# supply.net
KiCad netlist of a schematic drawn in EAGLE
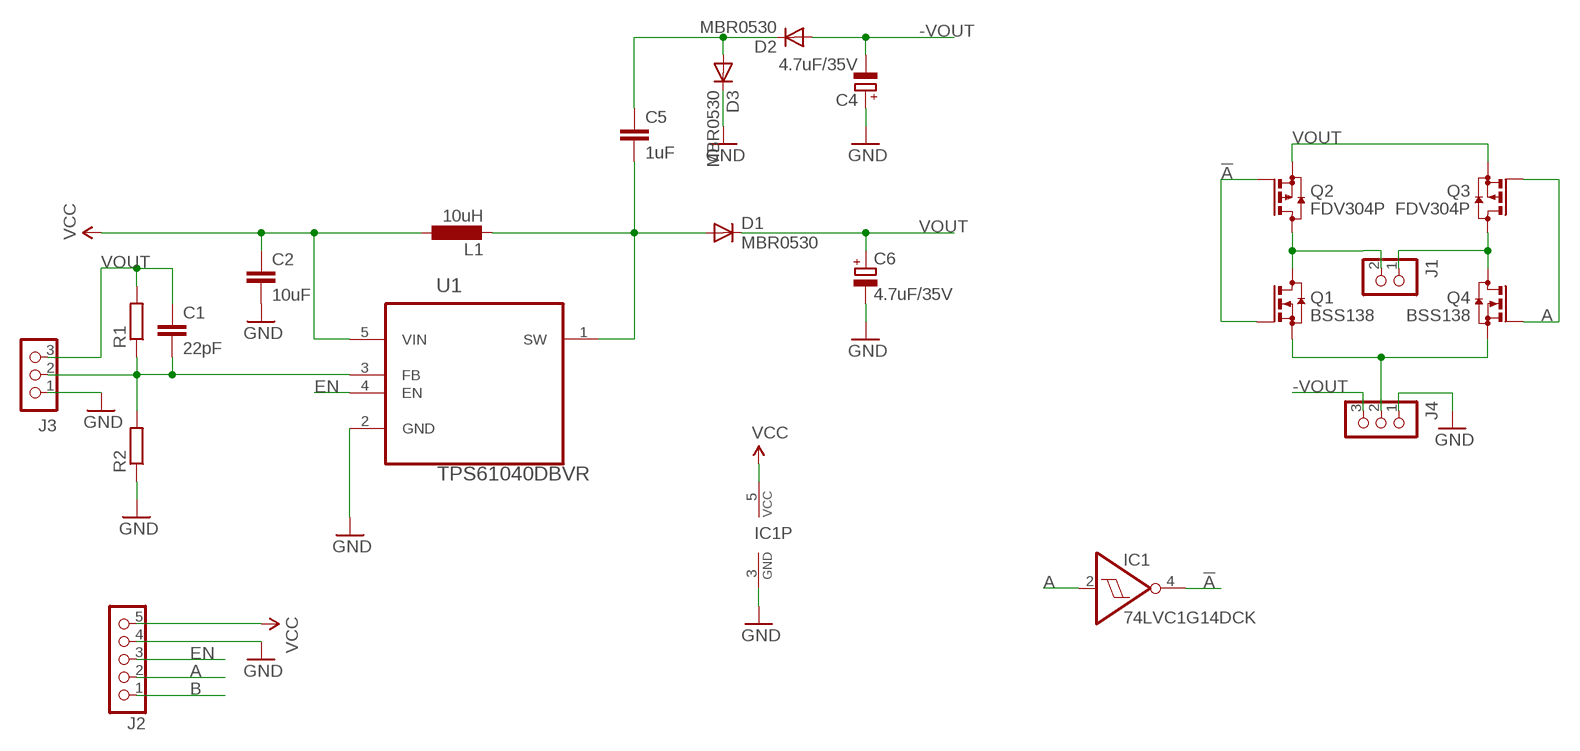
[diagram p0: schematic, sheet 1]

(export (version "E")
  (design (tool "Eeschema 10.0.6"))
  (components
    (comp (ref "C1")
      (value "22pF")
      (footprint "eagle-import:C0603")
      (libsource (lib "eagle-import") (part "C-EUC0603"))
    )
    (comp (ref "C2")
      (value "10uF")
      (footprint "eagle-import:C0603")
      (libsource (lib "eagle-import") (part "C-EUC0603"))
    )
    (comp (ref "C4")
      (value "4.7uF/35V")
      (footprint "eagle-import:140CLH-1010")
      (libsource (lib "eagle-import") (part "CPOL-EU140CLH-1010"))
    )
    (comp (ref "C5")
      (value "1uF")
      (footprint "eagle-import:C0603")
      (libsource (lib "eagle-import") (part "C-EUC0603"))
    )
    (comp (ref "C6")
      (value "4.7uF/35V")
      (footprint "eagle-import:140CLH-1010")
      (libsource (lib "eagle-import") (part "CPOL-EU140CLH-1010"))
    )
    (comp (ref "D1")
      (value "MBR0530")
      (footprint "eagle-import:SOD123")
      (libsource (lib "eagle-import") (part "DIODE-SOD123"))
    )
    (comp (ref "D2")
      (value "MBR0530")
      (footprint "eagle-import:SOD123")
      (libsource (lib "eagle-import") (part "DIODE-SOD123"))
    )
    (comp (ref "D3")
      (value "MBR0530")
      (footprint "eagle-import:SOD123")
      (libsource (lib "eagle-import") (part "DIODE-SOD123"))
    )
    (comp (ref "IC1")
      (value "74LVC1G14DCK")
      (footprint "eagle-import:SC70-5")
      (libsource (lib "eagle-import") (part "741G14DCKLVC"))
    )
    (comp (ref "J1")
      (value "CON_HEADER_1X02-PTH")
      (footprint "eagle-import:M1X2")
      (libsource (lib "eagle-import") (part "CON_HEADER_1X02-PTH"))
    )
    (comp (ref "J2")
      (value "CON_HEADER_1X05-PTH")
      (footprint "eagle-import:M1X5")
      (libsource (lib "eagle-import") (part "CON_HEADER_1X05-PTH"))
    )
    (comp (ref "J3")
      (value "CON_HEADER_1X03-PTH")
      (footprint "eagle-import:M1X3")
      (libsource (lib "eagle-import") (part "CON_HEADER_1X03-PTH"))
    )
    (comp (ref "J4")
      (value "CON_HEADER_1X03-PTH")
      (footprint "eagle-import:M1X3")
      (libsource (lib "eagle-import") (part "CON_HEADER_1X03-PTH"))
    )
    (comp (ref "L1")
      (value "10uH")
      (footprint "eagle-import:L2825P")
      (libsource (lib "eagle-import") (part "L-EUL2825P"))
    )
    (comp (ref "Q1")
      (value "BSS138")
      (footprint "eagle-import:SOT23")
      (libsource (lib "eagle-import") (part "BSS123"))
    )
    (comp (ref "Q2")
      (value "FDV304P")
      (footprint "eagle-import:SOT23")
      (libsource (lib "eagle-import") (part "BSS84"))
    )
    (comp (ref "Q3")
      (value "FDV304P")
      (footprint "eagle-import:SOT23")
      (libsource (lib "eagle-import") (part "BSS84"))
    )
    (comp (ref "Q4")
      (value "BSS138")
      (footprint "eagle-import:SOT23")
      (libsource (lib "eagle-import") (part "BSS123"))
    )
    (comp (ref "R1")
      (value "R-EU_R0603")
      (footprint "eagle-import:R0603")
      (libsource (lib "eagle-import") (part "R-EU_R0603"))
    )
    (comp (ref "R2")
      (value "R-EU_R0603")
      (footprint "eagle-import:R0603")
      (libsource (lib "eagle-import") (part "R-EU_R0603"))
    )
    (comp (ref "U1")
      (value "TPS61040DBVR")
      (footprint "eagle-import:SOT95P280X145-5N")
      (libsource (lib "eagle-import") (part "TPS61040DBVR"))
    )
  )
  (nets
    (net (code "1") (name "/-VOUT") (class "Default")
      (node (ref "C4") (pin "-") (pinfunction "-_-") (pintype "passive"))
      (node (ref "D2") (pin "A") (pinfunction "A_A") (pintype "passive"))
      (node (ref "J4") (pin "3") (pinfunction "3_3") (pintype "bidirectional"))
    )
    (net (code "2") (name "/A") (class "Default")
      (node (ref "IC1") (pin "2") (pinfunction "I_2") (pintype "input"))
      (node (ref "J2") (pin "2") (pinfunction "2_2") (pintype "bidirectional"))
      (node (ref "Q3") (pin "1") (pinfunction "G_1") (pintype "passive"))
      (node (ref "Q4") (pin "1") (pinfunction "G_1") (pintype "passive"))
    )
    (net (code "3") (name "/B") (class "Default")
      (node (ref "J2") (pin "1") (pinfunction "1_1") (pintype "bidirectional"))
    )
    (net (code "4") (name "/EN") (class "Default")
      (node (ref "J2") (pin "3") (pinfunction "3_3") (pintype "bidirectional"))
      (node (ref "U1") (pin "4") (pinfunction "EN_4") (pintype "input"))
    )
    (net (code "5") (name "/VOUT") (class "Default")
      (node (ref "C1") (pin "1") (pinfunction "1_1") (pintype "passive"))
      (node (ref "C6") (pin "+") (pinfunction "+_+") (pintype "passive"))
      (node (ref "D1") (pin "C") (pinfunction "C_C") (pintype "passive"))
      (node (ref "J3") (pin "3") (pinfunction "3_3") (pintype "bidirectional"))
      (node (ref "Q2") (pin "2") (pinfunction "S_2") (pintype "passive"))
      (node (ref "Q3") (pin "2") (pinfunction "S_2") (pintype "passive"))
      (node (ref "R1") (pin "2") (pinfunction "2_2") (pintype "passive"))
    )
    (net (code "6") (name "/~{A}") (class "Default")
      (node (ref "IC1") (pin "4") (pinfunction "O_4") (pintype "output"))
      (node (ref "Q1") (pin "1") (pinfunction "G_1") (pintype "passive"))
      (node (ref "Q2") (pin "1") (pinfunction "G_1") (pintype "passive"))
    )
    (net (code "7") (name "GND") (class "Default")
      (node (ref "C2") (pin "2") (pinfunction "2_2") (pintype "passive"))
      (node (ref "C4") (pin "+") (pinfunction "+_+") (pintype "passive"))
      (node (ref "C6") (pin "-") (pinfunction "-_-") (pintype "passive"))
      (node (ref "D3") (pin "C") (pinfunction "C_C") (pintype "passive"))
      (node (ref "IC1") (pin "3") (pinfunction "GND_3") (pintype "power_in"))
      (node (ref "J2") (pin "4") (pinfunction "4_4") (pintype "bidirectional"))
      (node (ref "J3") (pin "1") (pinfunction "1_1") (pintype "bidirectional"))
      (node (ref "J4") (pin "1") (pinfunction "1_1") (pintype "bidirectional"))
      (node (ref "R2") (pin "1") (pinfunction "1_1") (pintype "passive"))
      (node (ref "U1") (pin "2") (pinfunction "GND_2") (pintype "passive"))
    )
    (net (code "8") (name "Net-(C5-Pad1)") (class "Default")
      (node (ref "C5") (pin "1") (pinfunction "1_1") (pintype "passive"))
      (node (ref "D2") (pin "C") (pinfunction "C_C") (pintype "passive"))
      (node (ref "D3") (pin "A") (pinfunction "A_A") (pintype "passive"))
    )
    (net (code "9") (name "Net-(Q1-D)") (class "Default")
      (node (ref "J1") (pin "2") (pinfunction "2_2") (pintype "passive"))
      (node (ref "Q1") (pin "3") (pinfunction "D_3") (pintype "passive"))
      (node (ref "Q2") (pin "3") (pinfunction "D_3") (pintype "passive"))
    )
    (net (code "10") (name "Net-(Q1-S)") (class "Default")
      (node (ref "J4") (pin "2") (pinfunction "2_2") (pintype "bidirectional"))
      (node (ref "Q1") (pin "2") (pinfunction "S_2") (pintype "passive"))
      (node (ref "Q4") (pin "2") (pinfunction "S_2") (pintype "passive"))
    )
    (net (code "11") (name "Net-(Q3-D)") (class "Default")
      (node (ref "J1") (pin "1") (pinfunction "1_1") (pintype "passive"))
      (node (ref "Q3") (pin "3") (pinfunction "D_3") (pintype "passive"))
      (node (ref "Q4") (pin "3") (pinfunction "D_3") (pintype "passive"))
    )
    (net (code "12") (name "Net-(U1-FB)") (class "Default")
      (node (ref "C1") (pin "2") (pinfunction "2_2") (pintype "passive"))
      (node (ref "J3") (pin "2") (pinfunction "2_2") (pintype "bidirectional"))
      (node (ref "R1") (pin "1") (pinfunction "1_1") (pintype "passive"))
      (node (ref "R2") (pin "2") (pinfunction "2_2") (pintype "passive"))
      (node (ref "U1") (pin "3") (pinfunction "FB_3") (pintype "input"))
    )
    (net (code "13") (name "Net-(U1-SW)") (class "Default")
      (node (ref "C5") (pin "2") (pinfunction "2_2") (pintype "passive"))
      (node (ref "D1") (pin "A") (pinfunction "A_A") (pintype "passive"))
      (node (ref "L1") (pin "2") (pinfunction "2_2") (pintype "passive"))
      (node (ref "U1") (pin "1") (pinfunction "SW_1") (pintype "passive"))
    )
    (net (code "14") (name "VCC") (class "Default")
      (node (ref "C2") (pin "1") (pinfunction "1_1") (pintype "passive"))
      (node (ref "IC1") (pin "5") (pinfunction "VCC_5") (pintype "power_in"))
      (node (ref "J2") (pin "5") (pinfunction "5_5") (pintype "bidirectional"))
      (node (ref "L1") (pin "1") (pinfunction "1_1") (pintype "passive"))
      (node (ref "U1") (pin "5") (pinfunction "VIN_5") (pintype "power_in"))
    )
  )
)
